# mega.net
KiCad netlist of a schematic drawn in EAGLE
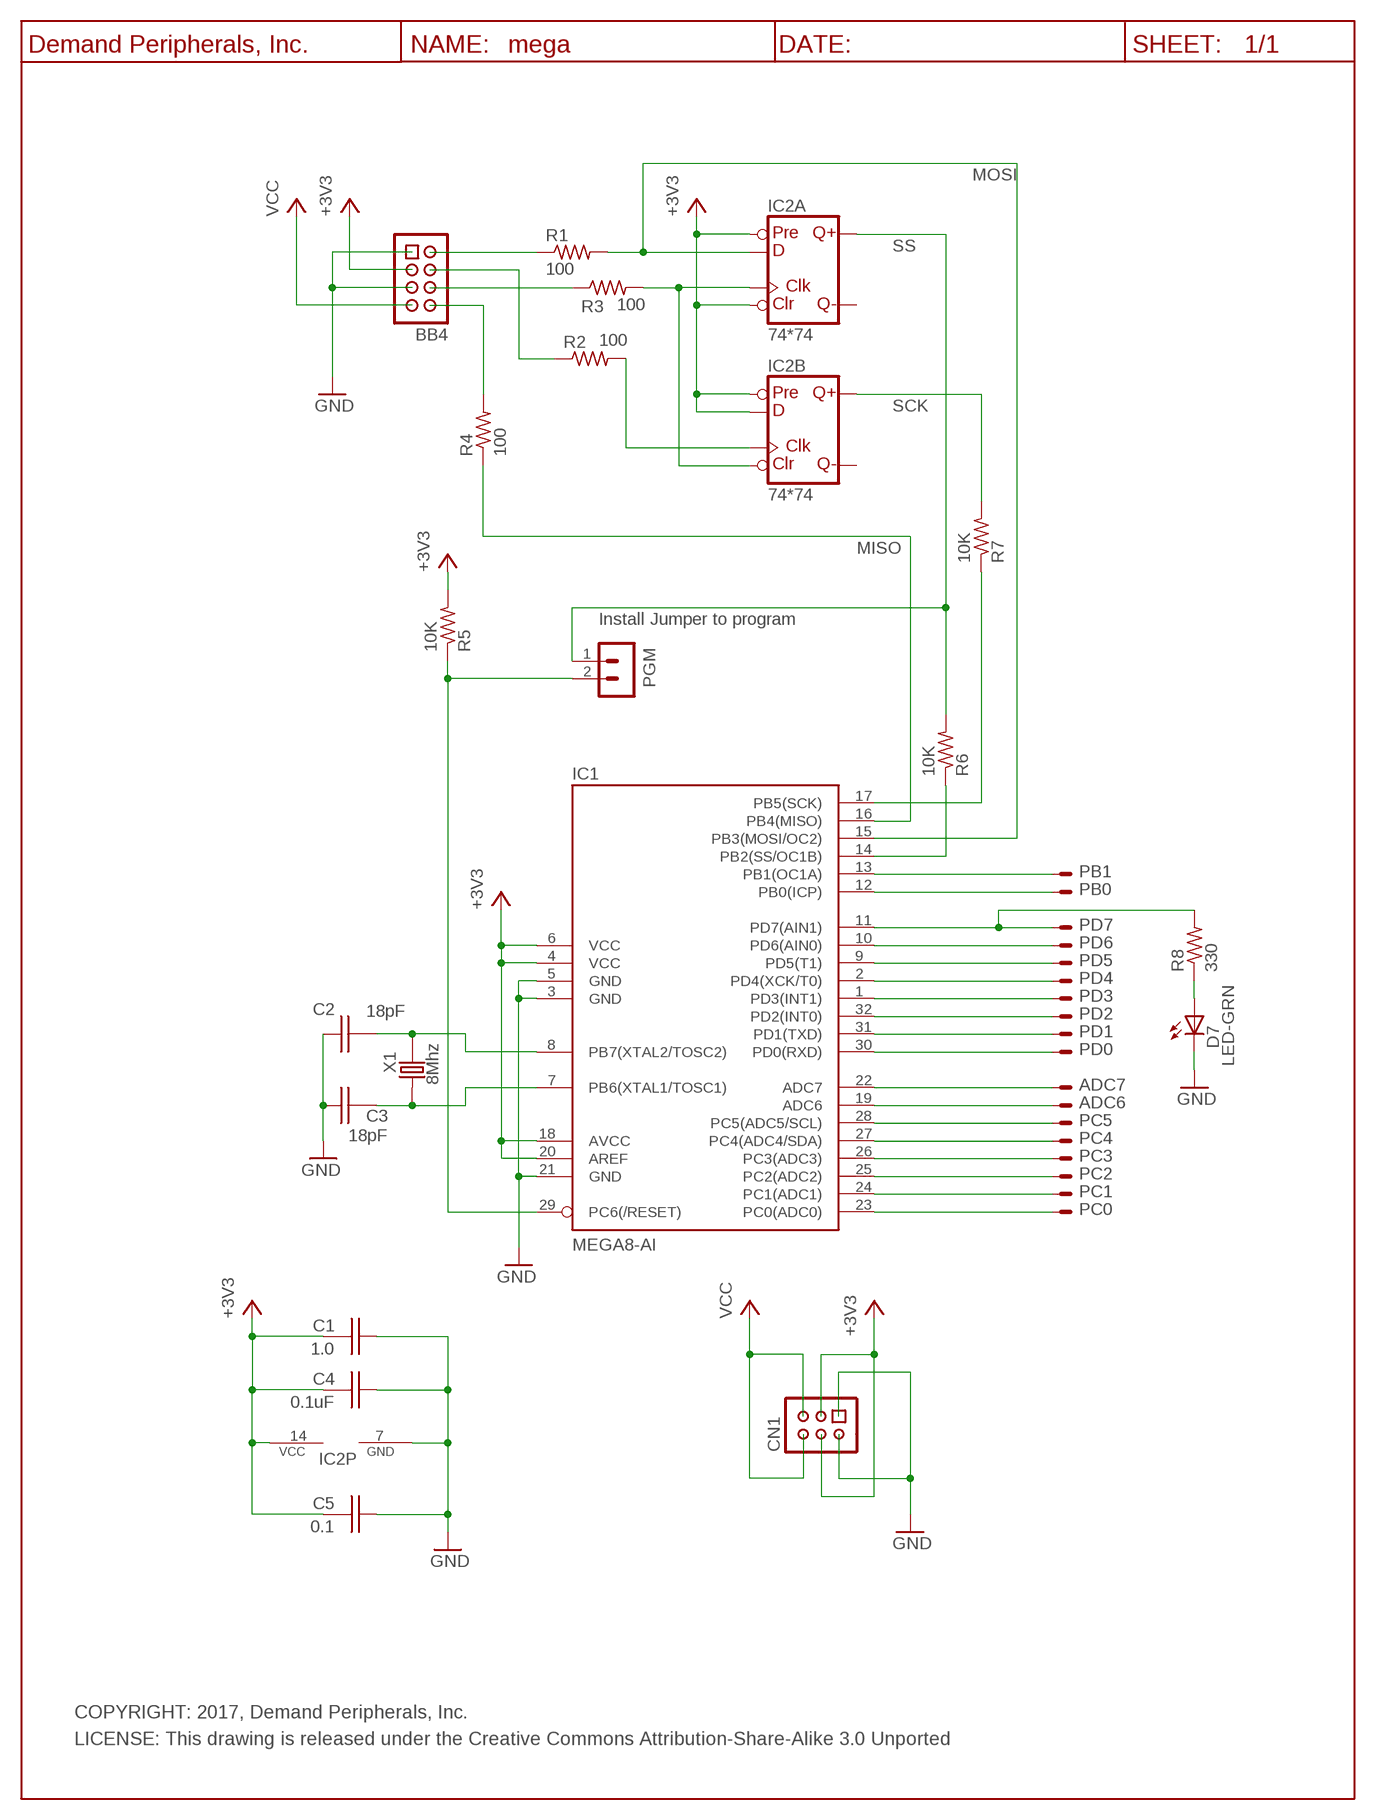
[diagram p0: schematic, sheet 1]

(export (version "E")
  (design (tool "Eeschema 10.0.6"))
  (components
    (comp (ref "ADC6")
      (value "PinHdr254-1(Option)")
      (footprint "eagle-import:PAD1")
      (libsource (lib "eagle-import") (part "PAD1"))
    )
    (comp (ref "ADC7")
      (value "PinHdr254-1(Option)")
      (footprint "eagle-import:PAD1")
      (libsource (lib "eagle-import") (part "PAD1"))
    )
    (comp (ref "BB4")
      (value "BB4_CON")
      (footprint "eagle-import:HDR-4X2")
      (libsource (lib "eagle-import") (part "HDR-4X2-SHR"))
    )
    (comp (ref "C1")
      (value "1.0")
      (footprint "eagle-import:C0603")
      (libsource (lib "eagle-import") (part "C1.0UF_C0603"))
    )
    (comp (ref "C2")
      (value "18pF")
      (footprint "eagle-import:C0603")
      (libsource (lib "eagle-import") (part "C18PF_C0603"))
    )
    (comp (ref "C3")
      (value "18pF")
      (footprint "eagle-import:C0603")
      (libsource (lib "eagle-import") (part "C18PF_C0603"))
    )
    (comp (ref "C4")
      (value "0.1uF")
      (footprint "eagle-import:C0603")
      (libsource (lib "eagle-import") (part "C0.1UF_C0603"))
    )
    (comp (ref "C5")
      (value "0.1")
      (footprint "eagle-import:C0603")
      (libsource (lib "eagle-import") (part "C0.1UF_C0603"))
    )
    (comp (ref "CN1")
      (value "HDR-3X2")
      (footprint "eagle-import:HDR-3X2")
      (libsource (lib "eagle-import") (part "HDR-3X2"))
    )
    (comp (ref "D7")
      (value "LED-GRN")
      (footprint "eagle-import:0805")
      (libsource (lib "eagle-import") (part "LED-0805-GRN"))
    )
    (comp (ref "IC1")
      (value "MEGA8-AI")
      (footprint "eagle-import:TQFP32-08")
      (libsource (lib "eagle-import") (part "MEGA8-AI"))
    )
    (comp (ref "IC2")
      (value "74*74")
      (footprint "eagle-import:TSSOP14")
      (libsource (lib "eagle-import") (part "74AHC74TS"))
    )
    (comp (ref "PB0")
      (value "PinHdr254-1(Option)")
      (footprint "eagle-import:PAD1")
      (libsource (lib "eagle-import") (part "PAD1"))
    )
    (comp (ref "PB1")
      (value "PinHdr254-1(Option)")
      (footprint "eagle-import:PAD1")
      (libsource (lib "eagle-import") (part "PAD1"))
    )
    (comp (ref "PC0")
      (value "PinHdr254-1(Option)")
      (footprint "eagle-import:PAD1")
      (libsource (lib "eagle-import") (part "PAD1"))
    )
    (comp (ref "PC1")
      (value "PinHdr254-1(Option)")
      (footprint "eagle-import:PAD1")
      (libsource (lib "eagle-import") (part "PAD1"))
    )
    (comp (ref "PC2")
      (value "PinHdr254-1(Option)")
      (footprint "eagle-import:PAD1")
      (libsource (lib "eagle-import") (part "PAD1"))
    )
    (comp (ref "PC3")
      (value "PinHdr254-1(Option)")
      (footprint "eagle-import:PAD1")
      (libsource (lib "eagle-import") (part "PAD1"))
    )
    (comp (ref "PC4")
      (value "PinHdr254-1(Option)")
      (footprint "eagle-import:PAD1")
      (libsource (lib "eagle-import") (part "PAD1"))
    )
    (comp (ref "PC5")
      (value "PinHdr254-1(Option)")
      (footprint "eagle-import:PAD1")
      (libsource (lib "eagle-import") (part "PAD1"))
    )
    (comp (ref "PD0")
      (value "PinHdr254-1(Option)")
      (footprint "eagle-import:PAD1")
      (libsource (lib "eagle-import") (part "PAD1"))
    )
    (comp (ref "PD1")
      (value "PinHdr254-1(Option)")
      (footprint "eagle-import:PAD1")
      (libsource (lib "eagle-import") (part "PAD1"))
    )
    (comp (ref "PD2")
      (value "PinHdr254-1(Option)")
      (footprint "eagle-import:PAD1")
      (libsource (lib "eagle-import") (part "PAD1"))
    )
    (comp (ref "PD3")
      (value "PinHdr254-1(Option)")
      (footprint "eagle-import:PAD1")
      (libsource (lib "eagle-import") (part "PAD1"))
    )
    (comp (ref "PD4")
      (value "PinHdr254-1(Option)")
      (footprint "eagle-import:PAD1")
      (libsource (lib "eagle-import") (part "PAD1"))
    )
    (comp (ref "PD5")
      (value "PinHdr254-1(Option)")
      (footprint "eagle-import:PAD1")
      (libsource (lib "eagle-import") (part "PAD1"))
    )
    (comp (ref "PD6")
      (value "PinHdr254-1(Option)")
      (footprint "eagle-import:PAD1")
      (libsource (lib "eagle-import") (part "PAD1"))
    )
    (comp (ref "PD7")
      (value "PinHdr254-1(Option)")
      (footprint "eagle-import:PAD1")
      (libsource (lib "eagle-import") (part "PAD1"))
    )
    (comp (ref "PGM")
      (value "PinHdr254-2")
      (footprint "eagle-import:HDR-2X1")
      (libsource (lib "eagle-import") (part "HDR-2X1-LCK"))
    )
    (comp (ref "R1")
      (value "100")
      (footprint "eagle-import:R0603")
      (libsource (lib "eagle-import") (part "R100_R0603"))
    )
    (comp (ref "R2")
      (value "100")
      (footprint "eagle-import:R0603")
      (libsource (lib "eagle-import") (part "R100_R0603"))
    )
    (comp (ref "R3")
      (value "100")
      (footprint "eagle-import:R0603")
      (libsource (lib "eagle-import") (part "R100_R0603"))
    )
    (comp (ref "R4")
      (value "100")
      (footprint "eagle-import:R0603")
      (libsource (lib "eagle-import") (part "R100_R0603"))
    )
    (comp (ref "R5")
      (value "10K")
      (footprint "eagle-import:R0603")
      (libsource (lib "eagle-import") (part "R10K_R0603"))
    )
    (comp (ref "R6")
      (value "10K")
      (footprint "eagle-import:R0603")
      (libsource (lib "eagle-import") (part "R10K_R0603"))
    )
    (comp (ref "R7")
      (value "10K")
      (footprint "eagle-import:R0603")
      (libsource (lib "eagle-import") (part "R10K_R0603"))
    )
    (comp (ref "R8")
      (value "330")
      (footprint "eagle-import:R0603")
      (libsource (lib "eagle-import") (part "R330_R0603"))
    )
    (comp (ref "U$1")
      (value "DP_FRAME_P")
      (footprint "eagle-import:P_FRAME")
      (libsource (lib "eagle-import") (part "DP_FRAME_P"))
    )
    (comp (ref "X1")
      (value "8Mhz")
      (footprint "eagle-import:NX5032")
      (libsource (lib "eagle-import") (part "NX5032-8MM5X32"))
    )
  )
  (nets
    (net (code "1") (name "+3V3") (class "Default")
      (node (ref "BB4") (pin "3") (pinfunction "3_3") (pintype "passive"))
      (node (ref "C1") (pin "2") (pinfunction "2_2") (pintype "passive"))
      (node (ref "C4") (pin "2") (pinfunction "2_2") (pintype "passive"))
      (node (ref "C5") (pin "2") (pinfunction "2_2") (pintype "passive"))
      (node (ref "CN1") (pin "3") (pinfunction "3_3") (pintype "passive"))
      (node (ref "CN1") (pin "4") (pinfunction "4_4") (pintype "passive"))
      (node (ref "IC1") (pin "18") (pinfunction "AVCC_18") (pintype "power_in"))
      (node (ref "IC1") (pin "20") (pinfunction "AREF_20") (pintype "passive"))
      (node (ref "IC1") (pin "4") (pinfunction "VCC_4") (pintype "power_in"))
      (node (ref "IC1") (pin "6") (pinfunction "VCC_6") (pintype "power_in"))
      (node (ref "IC2") (pin "1") (pinfunction "CLR_1") (pintype "input"))
      (node (ref "IC2") (pin "10") (pinfunction "PRE_10") (pintype "input"))
      (node (ref "IC2") (pin "12") (pinfunction "D_12") (pintype "input"))
      (node (ref "IC2") (pin "14") (pinfunction "VCC_14") (pintype "power_in"))
      (node (ref "IC2") (pin "4") (pinfunction "PRE_4") (pintype "input"))
      (node (ref "R5") (pin "2") (pinfunction "2_2") (pintype "passive"))
    )
    (net (code "2") (name "GND") (class "Default")
      (node (ref "BB4") (pin "1") (pinfunction "1_1") (pintype "passive"))
      (node (ref "BB4") (pin "5") (pinfunction "5_5") (pintype "passive"))
      (node (ref "C1") (pin "1") (pinfunction "1_1") (pintype "passive"))
      (node (ref "C2") (pin "1") (pinfunction "1_1") (pintype "passive"))
      (node (ref "C3") (pin "1") (pinfunction "1_1") (pintype "passive"))
      (node (ref "C4") (pin "1") (pinfunction "1_1") (pintype "passive"))
      (node (ref "C5") (pin "1") (pinfunction "1_1") (pintype "passive"))
      (node (ref "CN1") (pin "1") (pinfunction "1_1") (pintype "passive"))
      (node (ref "CN1") (pin "2") (pinfunction "2_2") (pintype "passive"))
      (node (ref "D7") (pin "C") (pinfunction "C_C") (pintype "passive"))
      (node (ref "IC1") (pin "21") (pinfunction "GND_21") (pintype "power_in"))
      (node (ref "IC1") (pin "3") (pinfunction "GND_3") (pintype "power_in"))
      (node (ref "IC1") (pin "5") (pinfunction "GND_5") (pintype "power_in"))
      (node (ref "IC2") (pin "7") (pinfunction "GND_7") (pintype "power_in"))
    )
    (net (code "3") (name "Net-(BB4-Pad2)") (class "Default")
      (node (ref "BB4") (pin "2") (pinfunction "2_2") (pintype "passive"))
      (node (ref "R1") (pin "1") (pinfunction "1_1") (pintype "passive"))
    )
    (net (code "4") (name "Net-(BB4-Pad4)") (class "Default")
      (node (ref "BB4") (pin "4") (pinfunction "4_4") (pintype "passive"))
      (node (ref "R2") (pin "1") (pinfunction "1_1") (pintype "passive"))
    )
    (net (code "5") (name "Net-(BB4-Pad6)") (class "Default")
      (node (ref "BB4") (pin "6") (pinfunction "6_6") (pintype "passive"))
      (node (ref "R3") (pin "1") (pinfunction "1_1") (pintype "passive"))
    )
    (net (code "6") (name "Net-(BB4-Pad8)") (class "Default")
      (node (ref "BB4") (pin "8") (pinfunction "8_8") (pintype "passive"))
      (node (ref "R4") (pin "2") (pinfunction "2_2") (pintype "passive"))
    )
    (net (code "7") (name "Net-(D7-PadA)") (class "Default")
      (node (ref "D7") (pin "A") (pinfunction "A_A") (pintype "passive"))
      (node (ref "R8") (pin "1") (pinfunction "1_1") (pintype "passive"))
    )
    (net (code "8") (name "Net-(IC1-ADC6)") (class "Default")
      (node (ref "ADC6") (pin "1") (pinfunction "1_1") (pintype "passive"))
      (node (ref "IC1") (pin "19") (pinfunction "ADC6_19") (pintype "bidirectional"))
    )
    (net (code "9") (name "Net-(IC1-ADC7)") (class "Default")
      (node (ref "ADC7") (pin "1") (pinfunction "1_1") (pintype "passive"))
      (node (ref "IC1") (pin "22") (pinfunction "ADC7_22") (pintype "bidirectional"))
    )
    (net (code "10") (name "Net-(IC1-PB0(ICP))") (class "Default")
      (node (ref "IC1") (pin "12") (pinfunction "PB0(ICP)_12") (pintype "bidirectional"))
      (node (ref "PB0") (pin "1") (pinfunction "1_1") (pintype "passive"))
    )
    (net (code "11") (name "Net-(IC1-PB1(OC1A))") (class "Default")
      (node (ref "IC1") (pin "13") (pinfunction "PB1(OC1A)_13") (pintype "bidirectional"))
      (node (ref "PB1") (pin "1") (pinfunction "1_1") (pintype "passive"))
    )
    (net (code "12") (name "Net-(IC1-PB2(SS{slash}OC1B))") (class "Default")
      (node (ref "IC1") (pin "14") (pinfunction "PB2(SS/OC1B)_14") (pintype "bidirectional"))
      (node (ref "R6") (pin "1") (pinfunction "1_1") (pintype "passive"))
    )
    (net (code "13") (name "Net-(IC1-PB3(MOSI{slash}OC2))") (class "Default")
      (node (ref "IC1") (pin "15") (pinfunction "PB3(MOSI/OC2)_15") (pintype "bidirectional"))
      (node (ref "IC2") (pin "2") (pinfunction "D_2") (pintype "input"))
      (node (ref "R1") (pin "2") (pinfunction "2_2") (pintype "passive"))
    )
    (net (code "14") (name "Net-(IC1-PB4(MISO))") (class "Default")
      (node (ref "IC1") (pin "16") (pinfunction "PB4(MISO)_16") (pintype "bidirectional"))
      (node (ref "R4") (pin "1") (pinfunction "1_1") (pintype "passive"))
    )
    (net (code "15") (name "Net-(IC1-PB5(SCK))") (class "Default")
      (node (ref "IC1") (pin "17") (pinfunction "PB5(SCK)_17") (pintype "bidirectional"))
      (node (ref "R7") (pin "1") (pinfunction "1_1") (pintype "passive"))
    )
    (net (code "16") (name "Net-(IC1-PB6(XTAL1{slash}TOSC1))") (class "Default")
      (node (ref "C3") (pin "2") (pinfunction "2_2") (pintype "passive"))
      (node (ref "IC1") (pin "7") (pinfunction "PB6(XTAL1/TOSC1)_7") (pintype "bidirectional"))
      (node (ref "X1") (pin "2") (pinfunction "2_2") (pintype "passive"))
    )
    (net (code "17") (name "Net-(IC1-PB7(XTAL2{slash}TOSC2))") (class "Default")
      (node (ref "C2") (pin "2") (pinfunction "2_2") (pintype "passive"))
      (node (ref "IC1") (pin "8") (pinfunction "PB7(XTAL2/TOSC2)_8") (pintype "bidirectional"))
      (node (ref "X1") (pin "1") (pinfunction "1_1") (pintype "passive"))
    )
    (net (code "18") (name "Net-(IC1-PC0(ADC0))") (class "Default")
      (node (ref "IC1") (pin "23") (pinfunction "PC0(ADC0)_23") (pintype "bidirectional"))
      (node (ref "PC0") (pin "1") (pinfunction "1_1") (pintype "passive"))
    )
    (net (code "19") (name "Net-(IC1-PC1(ADC1))") (class "Default")
      (node (ref "IC1") (pin "24") (pinfunction "PC1(ADC1)_24") (pintype "bidirectional"))
      (node (ref "PC1") (pin "1") (pinfunction "1_1") (pintype "passive"))
    )
    (net (code "20") (name "Net-(IC1-PC2(ADC2))") (class "Default")
      (node (ref "IC1") (pin "25") (pinfunction "PC2(ADC2)_25") (pintype "bidirectional"))
      (node (ref "PC2") (pin "1") (pinfunction "1_1") (pintype "passive"))
    )
    (net (code "21") (name "Net-(IC1-PC3(ADC3))") (class "Default")
      (node (ref "IC1") (pin "26") (pinfunction "PC3(ADC3)_26") (pintype "bidirectional"))
      (node (ref "PC3") (pin "1") (pinfunction "1_1") (pintype "passive"))
    )
    (net (code "22") (name "Net-(IC1-PC4(ADC4{slash}SDA))") (class "Default")
      (node (ref "IC1") (pin "27") (pinfunction "PC4(ADC4/SDA)_27") (pintype "bidirectional"))
      (node (ref "PC4") (pin "1") (pinfunction "1_1") (pintype "passive"))
    )
    (net (code "23") (name "Net-(IC1-PC5(ADC5{slash}SCL))") (class "Default")
      (node (ref "IC1") (pin "28") (pinfunction "PC5(ADC5/SCL)_28") (pintype "bidirectional"))
      (node (ref "PC5") (pin "1") (pinfunction "1_1") (pintype "passive"))
    )
    (net (code "24") (name "Net-(IC1-PC6({slash}RESET))") (class "Default")
      (node (ref "IC1") (pin "29") (pinfunction "PC6(/RESET)_29") (pintype "bidirectional"))
      (node (ref "PGM") (pin "2") (pinfunction "1_2") (pintype "passive"))
      (node (ref "R5") (pin "1") (pinfunction "1_1") (pintype "passive"))
    )
    (net (code "25") (name "Net-(IC1-PD0(RXD))") (class "Default")
      (node (ref "IC1") (pin "30") (pinfunction "PD0(RXD)_30") (pintype "bidirectional"))
      (node (ref "PD0") (pin "1") (pinfunction "1_1") (pintype "passive"))
    )
    (net (code "26") (name "Net-(IC1-PD1(TXD))") (class "Default")
      (node (ref "IC1") (pin "31") (pinfunction "PD1(TXD)_31") (pintype "bidirectional"))
      (node (ref "PD1") (pin "1") (pinfunction "1_1") (pintype "passive"))
    )
    (net (code "27") (name "Net-(IC1-PD2(INT0))") (class "Default")
      (node (ref "IC1") (pin "32") (pinfunction "PD2(INT0)_32") (pintype "bidirectional"))
      (node (ref "PD2") (pin "1") (pinfunction "1_1") (pintype "passive"))
    )
    (net (code "28") (name "Net-(IC1-PD3(INT1))") (class "Default")
      (node (ref "IC1") (pin "1") (pinfunction "PD3(INT1)_1") (pintype "bidirectional"))
      (node (ref "PD3") (pin "1") (pinfunction "1_1") (pintype "passive"))
    )
    (net (code "29") (name "Net-(IC1-PD4(XCK{slash}T0))") (class "Default")
      (node (ref "IC1") (pin "2") (pinfunction "PD4(XCK/T0)_2") (pintype "bidirectional"))
      (node (ref "PD4") (pin "1") (pinfunction "1_1") (pintype "passive"))
    )
    (net (code "30") (name "Net-(IC1-PD5(T1))") (class "Default")
      (node (ref "IC1") (pin "9") (pinfunction "PD5(T1)_9") (pintype "bidirectional"))
      (node (ref "PD5") (pin "1") (pinfunction "1_1") (pintype "passive"))
    )
    (net (code "31") (name "Net-(IC1-PD6(AIN0))") (class "Default")
      (node (ref "IC1") (pin "10") (pinfunction "PD6(AIN0)_10") (pintype "bidirectional"))
      (node (ref "PD6") (pin "1") (pinfunction "1_1") (pintype "passive"))
    )
    (net (code "32") (name "Net-(IC1-PD7(AIN1))") (class "Default")
      (node (ref "IC1") (pin "11") (pinfunction "PD7(AIN1)_11") (pintype "bidirectional"))
      (node (ref "PD7") (pin "1") (pinfunction "1_1") (pintype "passive"))
      (node (ref "R8") (pin "2") (pinfunction "2_2") (pintype "passive"))
    )
    (net (code "33") (name "Net-(IC2A-CLK)") (class "Default")
      (node (ref "IC2") (pin "13") (pinfunction "CLR_13") (pintype "input"))
      (node (ref "IC2") (pin "3") (pinfunction "CLK_3") (pintype "input"))
      (node (ref "R3") (pin "2") (pinfunction "2_2") (pintype "passive"))
    )
    (net (code "34") (name "Net-(IC2A-Q)") (class "Default")
      (node (ref "IC2") (pin "5") (pinfunction "Q_5") (pintype "output"))
      (node (ref "PGM") (pin "1") (pinfunction "2_1") (pintype "passive"))
      (node (ref "R6") (pin "2") (pinfunction "2_2") (pintype "passive"))
    )
    (net (code "35") (name "Net-(IC2B-CLK)") (class "Default")
      (node (ref "IC2") (pin "11") (pinfunction "CLK_11") (pintype "input"))
      (node (ref "R2") (pin "2") (pinfunction "2_2") (pintype "passive"))
    )
    (net (code "36") (name "Net-(IC2B-Q)") (class "Default")
      (node (ref "IC2") (pin "9") (pinfunction "Q_9") (pintype "output"))
      (node (ref "R7") (pin "2") (pinfunction "2_2") (pintype "passive"))
    )
    (net (code "37") (name "VCC") (class "Default")
      (node (ref "BB4") (pin "7") (pinfunction "7_7") (pintype "passive"))
      (node (ref "CN1") (pin "5") (pinfunction "5_5") (pintype "passive"))
      (node (ref "CN1") (pin "6") (pinfunction "6_6") (pintype "passive"))
    )
    (net (code "38") (name "unconnected-(IC2A-~{Q}-Pad6)") (class "Default")
      (node (ref "IC2") (pin "6") (pinfunction "~{Q}_6") (pintype "output"))
    )
    (net (code "39") (name "unconnected-(IC2B-~{Q}-Pad8)") (class "Default")
      (node (ref "IC2") (pin "8") (pinfunction "~{Q}_8") (pintype "output"))
    )
  )
)
